# FE1-1S.net
KiCad netlist of a schematic drawn in EAGLE
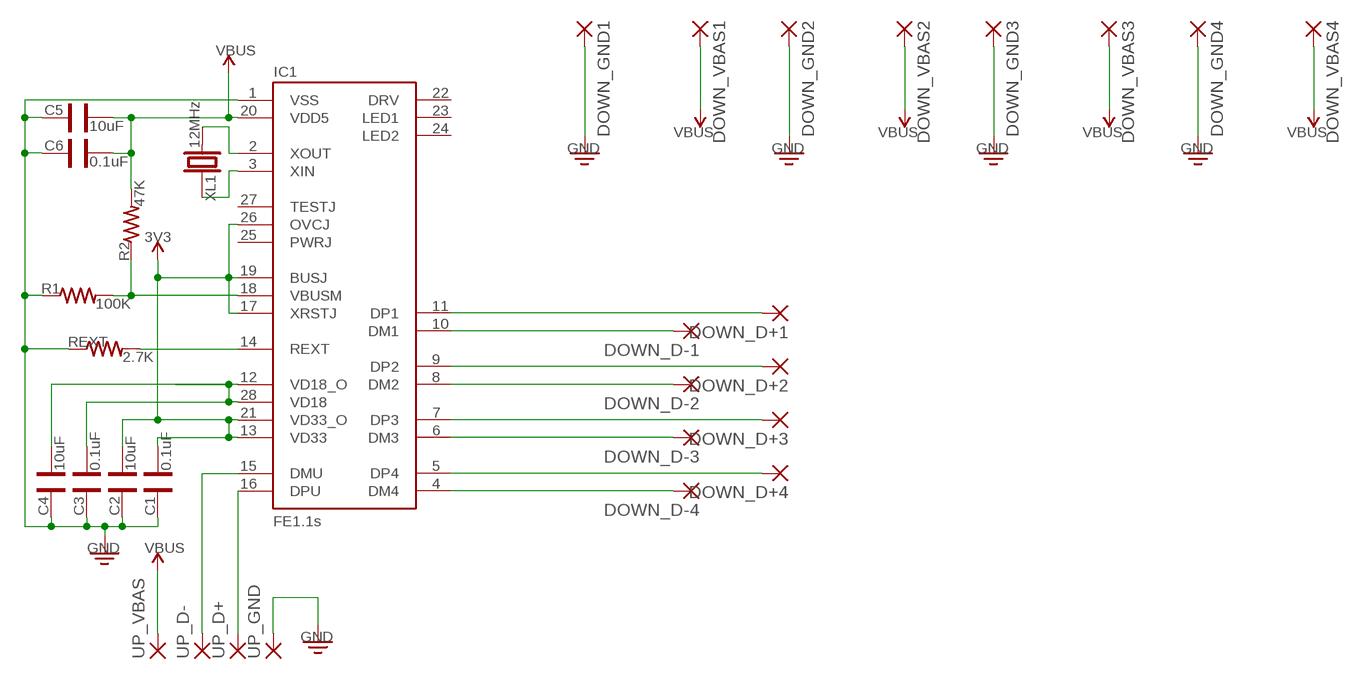
[diagram p0: schematic, sheet 1]

(export (version "E")
  (design (tool "Eeschema 10.0.6"))
  (components
    (comp (ref "C1")
      (value "0.1uF")
      (footprint "eagle-import:CAP-0603")
      (libsource (lib "eagle-import") (part "CAP0603"))
    )
    (comp (ref "C2")
      (value "10uF")
      (footprint "eagle-import:CAP-0603")
      (libsource (lib "eagle-import") (part "CAP0603"))
    )
    (comp (ref "C3")
      (value "0.1uF")
      (footprint "eagle-import:CAP-0603")
      (libsource (lib "eagle-import") (part "CAP0603"))
    )
    (comp (ref "C4")
      (value "10uF")
      (footprint "eagle-import:CAP-0603")
      (libsource (lib "eagle-import") (part "CAP0603"))
    )
    (comp (ref "C5")
      (value "10uF")
      (footprint "eagle-import:CAP-0603")
      (libsource (lib "eagle-import") (part "CAP0603"))
    )
    (comp (ref "C6")
      (value "0.1uF")
      (footprint "eagle-import:CAP-0603")
      (libsource (lib "eagle-import") (part "CAP0603"))
    )
    (comp (ref "DOWN_D+1")
      (value "SMD2")
      (footprint "eagle-import:SMD1,27-2,54")
      (libsource (lib "eagle-import") (part "SMD2"))
    )
    (comp (ref "DOWN_D+2")
      (value "SMD2")
      (footprint "eagle-import:SMD1,27-2,54")
      (libsource (lib "eagle-import") (part "SMD2"))
    )
    (comp (ref "DOWN_D+3")
      (value "SMD2")
      (footprint "eagle-import:SMD1,27-2,54")
      (libsource (lib "eagle-import") (part "SMD2"))
    )
    (comp (ref "DOWN_D+4")
      (value "SMD2")
      (footprint "eagle-import:SMD1,27-2,54")
      (libsource (lib "eagle-import") (part "SMD2"))
    )
    (comp (ref "DOWN_D-1")
      (value "SMD2")
      (footprint "eagle-import:SMD1,27-2,54")
      (libsource (lib "eagle-import") (part "SMD2"))
    )
    (comp (ref "DOWN_D-2")
      (value "SMD2")
      (footprint "eagle-import:SMD1,27-2,54")
      (libsource (lib "eagle-import") (part "SMD2"))
    )
    (comp (ref "DOWN_D-3")
      (value "SMD2")
      (footprint "eagle-import:SMD1,27-2,54")
      (libsource (lib "eagle-import") (part "SMD2"))
    )
    (comp (ref "DOWN_D-4")
      (value "SMD2")
      (footprint "eagle-import:SMD1,27-2,54")
      (libsource (lib "eagle-import") (part "SMD2"))
    )
    (comp (ref "DOWN_GND1")
      (value "SMD2")
      (footprint "eagle-import:SMD1,27-2,54")
      (libsource (lib "eagle-import") (part "SMD2"))
    )
    (comp (ref "DOWN_GND2")
      (value "SMD2")
      (footprint "eagle-import:SMD1,27-2,54")
      (libsource (lib "eagle-import") (part "SMD2"))
    )
    (comp (ref "DOWN_GND3")
      (value "SMD2")
      (footprint "eagle-import:SMD1,27-2,54")
      (libsource (lib "eagle-import") (part "SMD2"))
    )
    (comp (ref "DOWN_GND4")
      (value "SMD2")
      (footprint "eagle-import:SMD1,27-2,54")
      (libsource (lib "eagle-import") (part "SMD2"))
    )
    (comp (ref "DOWN_VBAS1")
      (value "SMD2")
      (footprint "eagle-import:SMD1,27-2,54")
      (libsource (lib "eagle-import") (part "SMD2"))
    )
    (comp (ref "DOWN_VBAS2")
      (value "SMD2")
      (footprint "eagle-import:SMD1,27-2,54")
      (libsource (lib "eagle-import") (part "SMD2"))
    )
    (comp (ref "DOWN_VBAS3")
      (value "SMD2")
      (footprint "eagle-import:SMD1,27-2,54")
      (libsource (lib "eagle-import") (part "SMD2"))
    )
    (comp (ref "DOWN_VBAS4")
      (value "SMD2")
      (footprint "eagle-import:SMD1,27-2,54")
      (libsource (lib "eagle-import") (part "SMD2"))
    )
    (comp (ref "IC1")
      (value "FE1.1S")
      (footprint "eagle-import:FE1.1S_SSOP-28")
      (libsource (lib "eagle-import") (part "FE1.1S"))
    )
    (comp (ref "R1")
      (value "100K")
      (footprint "eagle-import:RES-0603")
      (libsource (lib "eagle-import") (part "RES0603"))
    )
    (comp (ref "R2")
      (value "47K")
      (footprint "eagle-import:RES-0603")
      (libsource (lib "eagle-import") (part "RES0603"))
    )
    (comp (ref "REXT")
      (value "2.7K")
      (footprint "eagle-import:RES-0603")
      (libsource (lib "eagle-import") (part "RES0603"))
    )
    (comp (ref "UP_D+")
      (value "SMD2")
      (footprint "eagle-import:SMD1,27-2,54")
      (libsource (lib "eagle-import") (part "SMD2"))
    )
    (comp (ref "UP_D-")
      (value "SMD2")
      (footprint "eagle-import:SMD1,27-2,54")
      (libsource (lib "eagle-import") (part "SMD2"))
    )
    (comp (ref "UP_GND")
      (value "SMD2")
      (footprint "eagle-import:SMD1,27-2,54")
      (libsource (lib "eagle-import") (part "SMD2"))
    )
    (comp (ref "UP_VBAS")
      (value "SMD2")
      (footprint "eagle-import:SMD1,27-2,54")
      (libsource (lib "eagle-import") (part "SMD2"))
    )
    (comp (ref "XL1")
      (value "12MHz")
      (footprint "eagle-import:HC49S")
      (libsource (lib "eagle-import") (part "CRYSTALHC49S"))
    )
  )
  (nets
    (net (code "1") (name "3V3") (class "Default")
      (node (ref "C1") (pin "1") (pinfunction "1_1") (pintype "passive"))
      (node (ref "C2") (pin "1") (pinfunction "1_1") (pintype "passive"))
      (node (ref "IC1") (pin "13") (pinfunction "VD33_13") (pintype "bidirectional"))
      (node (ref "IC1") (pin "17") (pinfunction "XRSTJ_17") (pintype "bidirectional"))
      (node (ref "IC1") (pin "19") (pinfunction "BUSJ_19") (pintype "bidirectional"))
      (node (ref "IC1") (pin "21") (pinfunction "VD33_O_21") (pintype "bidirectional"))
      (node (ref "IC1") (pin "26") (pinfunction "OVCJ_26") (pintype "bidirectional"))
    )
    (net (code "2") (name "GND") (class "Default")
      (node (ref "C1") (pin "2") (pinfunction "2_2") (pintype "passive"))
      (node (ref "C2") (pin "2") (pinfunction "2_2") (pintype "passive"))
      (node (ref "C3") (pin "2") (pinfunction "2_2") (pintype "passive"))
      (node (ref "C4") (pin "2") (pinfunction "2_2") (pintype "passive"))
      (node (ref "C5") (pin "2") (pinfunction "2_2") (pintype "passive"))
      (node (ref "C6") (pin "2") (pinfunction "2_2") (pintype "passive"))
      (node (ref "DOWN_GND1") (pin "1") (pinfunction "P_1") (pintype "passive"))
      (node (ref "DOWN_GND2") (pin "1") (pinfunction "P_1") (pintype "passive"))
      (node (ref "DOWN_GND3") (pin "1") (pinfunction "P_1") (pintype "passive"))
      (node (ref "DOWN_GND4") (pin "1") (pinfunction "P_1") (pintype "passive"))
      (node (ref "IC1") (pin "1") (pinfunction "VSS_1") (pintype "bidirectional"))
      (node (ref "R1") (pin "1") (pinfunction "1_1") (pintype "passive"))
      (node (ref "REXT") (pin "1") (pinfunction "1_1") (pintype "passive"))
      (node (ref "UP_GND") (pin "1") (pinfunction "P_1") (pintype "passive"))
    )
    (net (code "3") (name "Net-(DOWN_D+1-P)") (class "Default")
      (node (ref "DOWN_D+1") (pin "1") (pinfunction "P_1") (pintype "passive"))
      (node (ref "IC1") (pin "11") (pinfunction "DP1_11") (pintype "bidirectional"))
    )
    (net (code "4") (name "Net-(DOWN_D+2-P)") (class "Default")
      (node (ref "DOWN_D+2") (pin "1") (pinfunction "P_1") (pintype "passive"))
      (node (ref "IC1") (pin "9") (pinfunction "DP2_9") (pintype "bidirectional"))
    )
    (net (code "5") (name "Net-(DOWN_D+3-P)") (class "Default")
      (node (ref "DOWN_D+3") (pin "1") (pinfunction "P_1") (pintype "passive"))
      (node (ref "IC1") (pin "7") (pinfunction "DP3_7") (pintype "bidirectional"))
    )
    (net (code "6") (name "Net-(DOWN_D+4-P)") (class "Default")
      (node (ref "DOWN_D+4") (pin "1") (pinfunction "P_1") (pintype "passive"))
      (node (ref "IC1") (pin "5") (pinfunction "DP4_5") (pintype "bidirectional"))
    )
    (net (code "7") (name "Net-(DOWN_D-1-P)") (class "Default")
      (node (ref "DOWN_D-1") (pin "1") (pinfunction "P_1") (pintype "passive"))
      (node (ref "IC1") (pin "10") (pinfunction "DM1_10") (pintype "bidirectional"))
    )
    (net (code "8") (name "Net-(DOWN_D-2-P)") (class "Default")
      (node (ref "DOWN_D-2") (pin "1") (pinfunction "P_1") (pintype "passive"))
      (node (ref "IC1") (pin "8") (pinfunction "DM2_8") (pintype "bidirectional"))
    )
    (net (code "9") (name "Net-(DOWN_D-3-P)") (class "Default")
      (node (ref "DOWN_D-3") (pin "1") (pinfunction "P_1") (pintype "passive"))
      (node (ref "IC1") (pin "6") (pinfunction "DM3_6") (pintype "bidirectional"))
    )
    (net (code "10") (name "Net-(DOWN_D-4-P)") (class "Default")
      (node (ref "DOWN_D-4") (pin "1") (pinfunction "P_1") (pintype "passive"))
      (node (ref "IC1") (pin "4") (pinfunction "DM4_4") (pintype "bidirectional"))
    )
    (net (code "11") (name "Net-(IC1-DMU)") (class "Default")
      (node (ref "IC1") (pin "15") (pinfunction "DMU_15") (pintype "bidirectional"))
      (node (ref "UP_D-") (pin "1") (pinfunction "P_1") (pintype "passive"))
    )
    (net (code "12") (name "Net-(IC1-DPU)") (class "Default")
      (node (ref "IC1") (pin "16") (pinfunction "DPU_16") (pintype "bidirectional"))
      (node (ref "UP_D+") (pin "1") (pinfunction "P_1") (pintype "passive"))
    )
    (net (code "13") (name "Net-(IC1-REXT)") (class "Default")
      (node (ref "IC1") (pin "14") (pinfunction "REXT_14") (pintype "bidirectional"))
      (node (ref "REXT") (pin "2") (pinfunction "2_2") (pintype "passive"))
    )
    (net (code "14") (name "Net-(IC1-VBUSM)") (class "Default")
      (node (ref "IC1") (pin "18") (pinfunction "VBUSM_18") (pintype "bidirectional"))
      (node (ref "R1") (pin "2") (pinfunction "2_2") (pintype "passive"))
      (node (ref "R2") (pin "1") (pinfunction "1_1") (pintype "passive"))
    )
    (net (code "15") (name "Net-(IC1-VD18)") (class "Default")
      (node (ref "C3") (pin "1") (pinfunction "1_1") (pintype "passive"))
      (node (ref "C4") (pin "1") (pinfunction "1_1") (pintype "passive"))
      (node (ref "IC1") (pin "12") (pinfunction "VD18_O_12") (pintype "bidirectional"))
      (node (ref "IC1") (pin "28") (pinfunction "VD18_28") (pintype "bidirectional"))
    )
    (net (code "16") (name "Net-(IC1-XIN)") (class "Default")
      (node (ref "IC1") (pin "3") (pinfunction "XIN_3") (pintype "bidirectional"))
      (node (ref "XL1") (pin "1") (pinfunction "1_1") (pintype "passive"))
    )
    (net (code "17") (name "Net-(IC1-XOUT)") (class "Default")
      (node (ref "IC1") (pin "2") (pinfunction "XOUT_2") (pintype "bidirectional"))
      (node (ref "XL1") (pin "2") (pinfunction "2_2") (pintype "passive"))
    )
    (net (code "18") (name "VBUS") (class "Default")
      (node (ref "C5") (pin "1") (pinfunction "1_1") (pintype "passive"))
      (node (ref "C6") (pin "1") (pinfunction "1_1") (pintype "passive"))
      (node (ref "DOWN_VBAS1") (pin "1") (pinfunction "P_1") (pintype "passive"))
      (node (ref "DOWN_VBAS2") (pin "1") (pinfunction "P_1") (pintype "passive"))
      (node (ref "DOWN_VBAS3") (pin "1") (pinfunction "P_1") (pintype "passive"))
      (node (ref "DOWN_VBAS4") (pin "1") (pinfunction "P_1") (pintype "passive"))
      (node (ref "IC1") (pin "20") (pinfunction "VDD5_20") (pintype "bidirectional"))
      (node (ref "R2") (pin "2") (pinfunction "2_2") (pintype "passive"))
      (node (ref "UP_VBAS") (pin "1") (pinfunction "P_1") (pintype "passive"))
    )
    (net (code "19") (name "unconnected-(IC1-DRV-Pad22)") (class "Default")
      (node (ref "IC1") (pin "22") (pinfunction "DRV_22") (pintype "bidirectional"))
    )
    (net (code "20") (name "unconnected-(IC1-LED1-Pad23)") (class "Default")
      (node (ref "IC1") (pin "23") (pinfunction "LED1_23") (pintype "bidirectional"))
    )
    (net (code "21") (name "unconnected-(IC1-LED2-Pad24)") (class "Default")
      (node (ref "IC1") (pin "24") (pinfunction "LED2_24") (pintype "bidirectional"))
    )
    (net (code "22") (name "unconnected-(IC1-PWRJ-Pad25)") (class "Default")
      (node (ref "IC1") (pin "25") (pinfunction "PWRJ_25") (pintype "bidirectional"))
    )
    (net (code "23") (name "unconnected-(IC1-TESTJ-Pad27)") (class "Default")
      (node (ref "IC1") (pin "27") (pinfunction "TESTJ_27") (pintype "bidirectional"))
    )
  )
)
